# MCU_STM32.net
KiCad netlist of a schematic drawn in Altium Designer
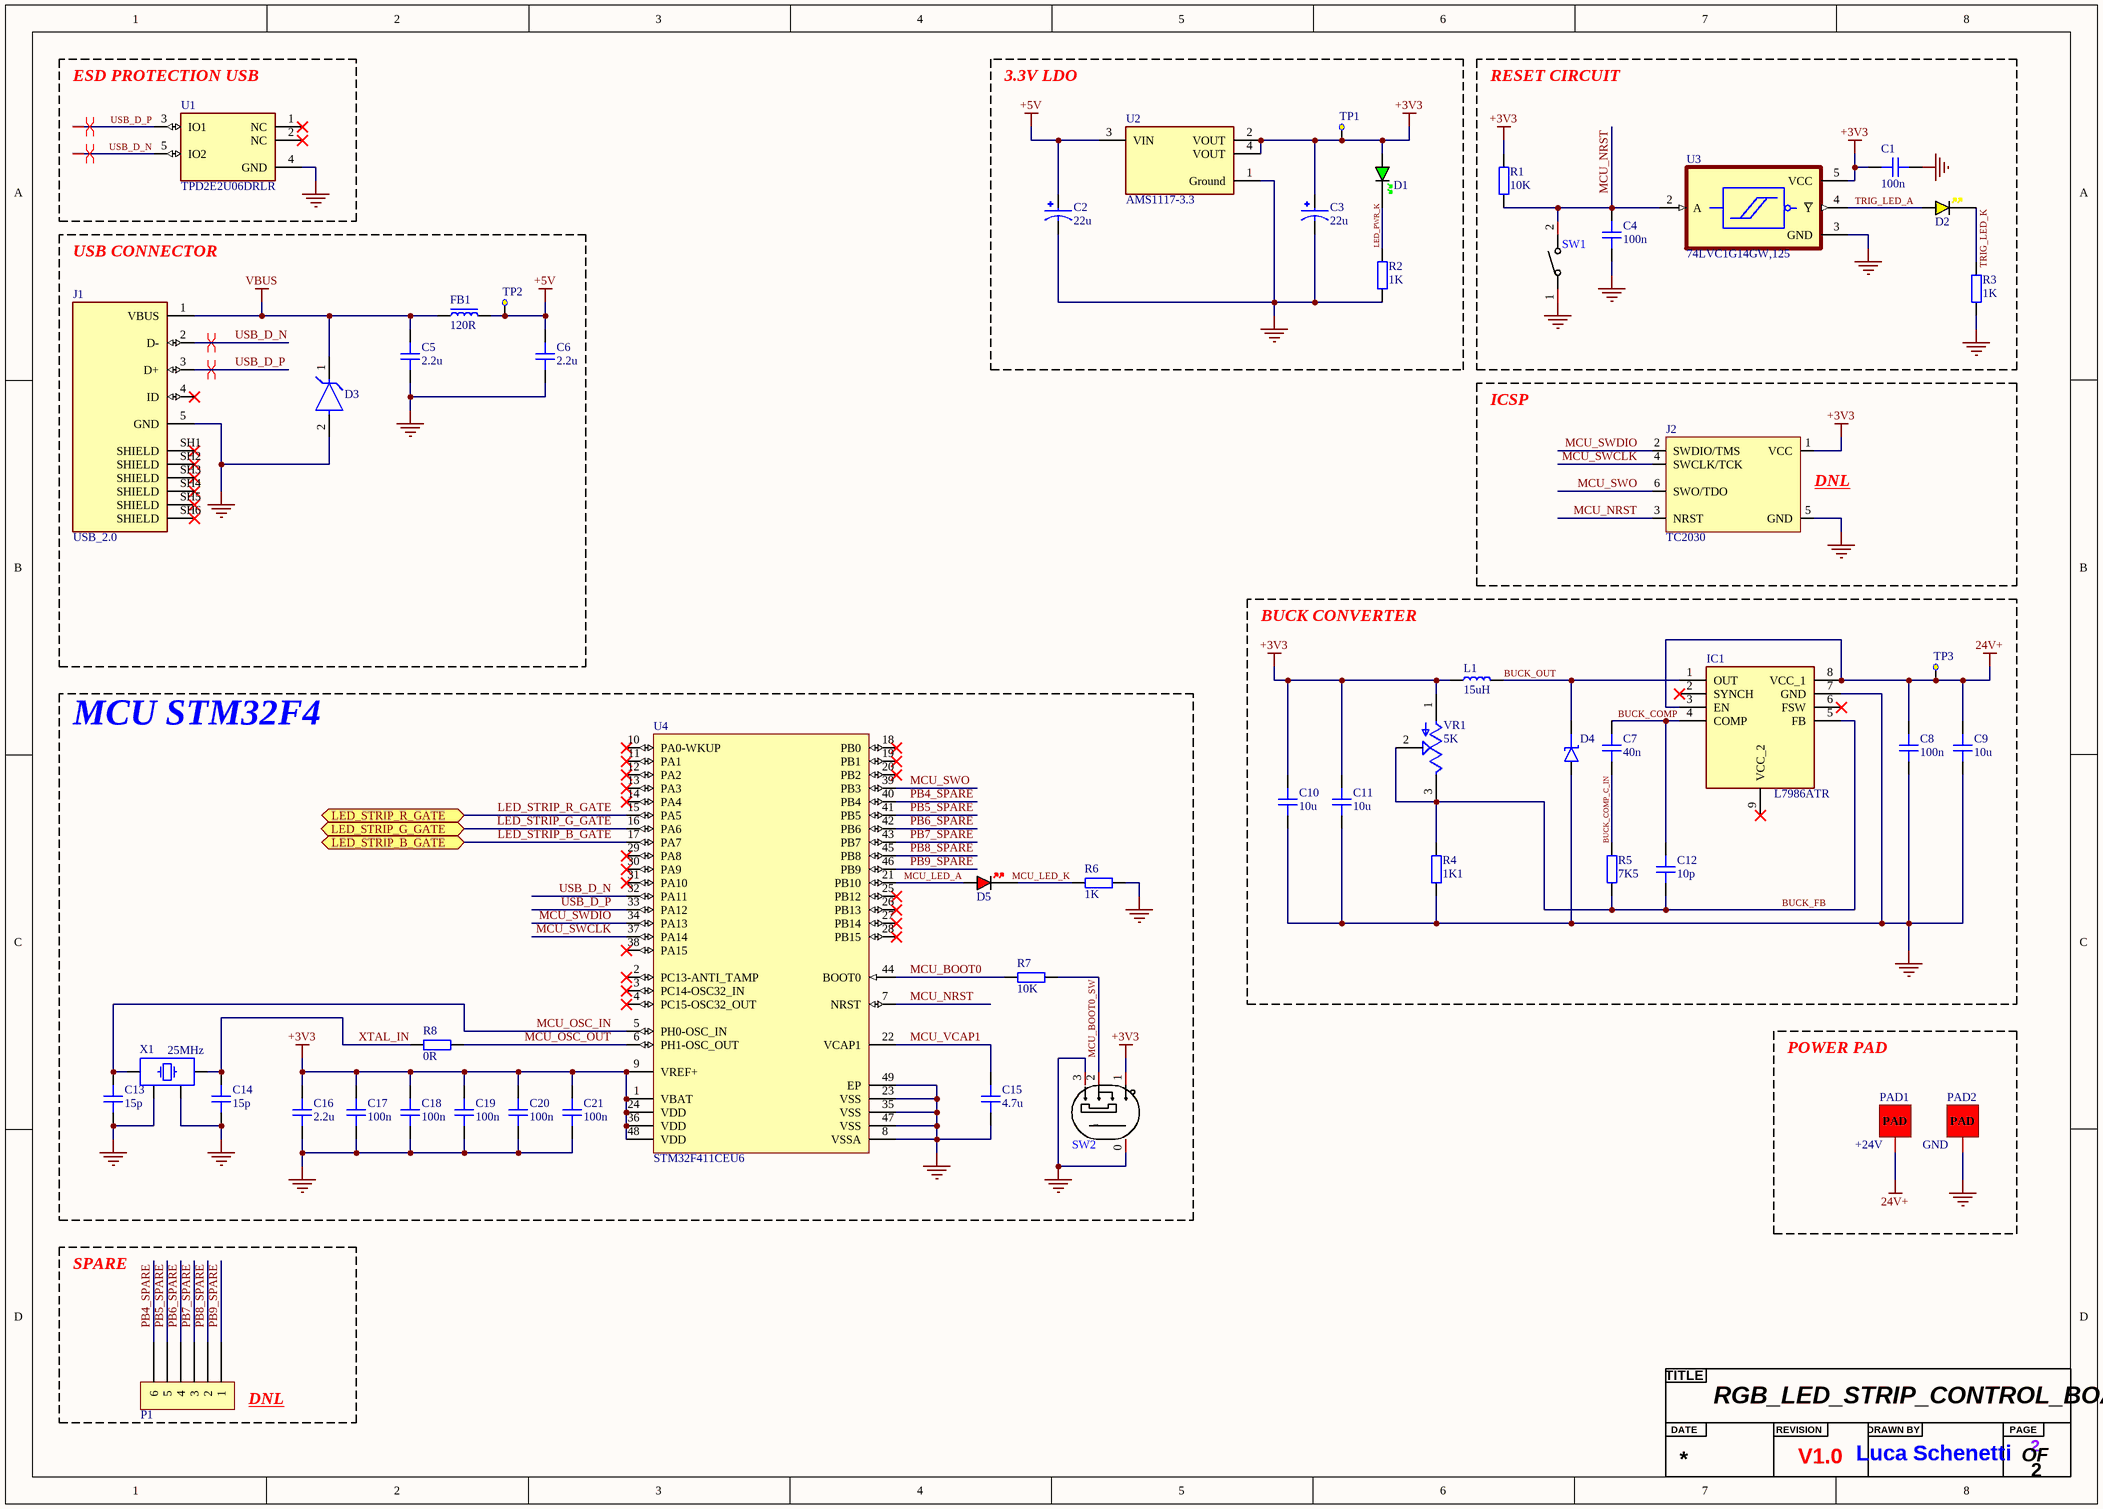
[diagram p0: MCU_STM32.SchDoc]

(export (version "E")
  (design (tool "Eeschema 10.0.6"))
  (components
    (comp (ref "C1")
      (value "100n")
      (footprint "CAP_0402")
      (description "Capacitor SMD 0402 [C1525]")
      (libsource (lib "Schematic-Lib-PhilsLab") (part "CAP_0402"))
    )
    (comp (ref "C2")
      (value "22u")
      (footprint "CAP_EEE1EA220WR")
      (description "Cap Aluminum Lytic 22uF [C2887274]")
      (fields (field (name "MF") "Panasonic") (field (name "DIGI-KEY_PART_NUMBER") "PCE3900TR-ND"))
      (libsource (lib "EEE1EA220WR") (part "EEE1EA220WR"))
    )
    (comp (ref "C3")
      (value "22u")
      (footprint "CAP_EEE1EA220WR")
      (description "Cap Aluminum Lytic 22uF [C2887274]")
      (fields (field (name "MF") "Panasonic") (field (name "DIGI-KEY_PART_NUMBER") "PCE3900TR-ND"))
      (libsource (lib "EEE1EA220WR") (part "EEE1EA220WR"))
    )
    (comp (ref "C4")
      (value "100n")
      (footprint "CAP_0402")
      (description "Capacitor SMD 0402 [C1525]")
      (libsource (lib "Schematic-Lib-PhilsLab") (part "CAP_0402"))
    )
    (comp (ref "C5")
      (value "2.2u")
      (footprint "CAP_0603")
      (description "Capacitor SMD 0603 [C23630]")
      (libsource (lib "Schematic-Lib-PhilsLab") (part "CAP_0603"))
    )
    (comp (ref "C6")
      (value "2.2u")
      (footprint "CAP_0603")
      (description "Capacitor SMD 0603 [C23630]")
      (libsource (lib "Schematic-Lib-PhilsLab") (part "CAP_0603"))
    )
    (comp (ref "C7")
      (value "40n")
      (footprint "CAP_0805")
      (description "Capacitor SMD 0805 [C502151]")
      (libsource (lib "Schematic-Lib-PhilsLab") (part "CAP_0805"))
    )
    (comp (ref "C8")
      (value "100n")
      (footprint "CAP_0805")
      (description "Capacitor SMD [C49678]")
      (libsource (lib "Schematic-Lib-PhilsLab") (part "CAP_0805"))
    )
    (comp (ref "C9")
      (value "10u")
      (footprint "CAP_0805")
      (description "Capacitor SMD [C440198]")
      (libsource (lib "Schematic-Lib-PhilsLab") (part "CAP_0805"))
    )
    (comp (ref "C10")
      (value "10u")
      (footprint "CAP_0805")
      (description "Capacitor SMD [C440198]")
      (libsource (lib "Schematic-Lib-PhilsLab") (part "CAP_0805"))
    )
    (comp (ref "C11")
      (value "10u")
      (footprint "CAP_0805")
      (description "Capacitor SMD [C440198]")
      (libsource (lib "Schematic-Lib-PhilsLab") (part "CAP_0805"))
    )
    (comp (ref "C12")
      (value "10p")
      (footprint "CAP_0402")
      (description "Capacitor SMD 0402 [C32949]")
      (libsource (lib "Schematic-Lib-PhilsLab") (part "CAP_0402"))
    )
    (comp (ref "C13")
      (value "15p")
      (footprint "CAP_0402")
      (description "Capacitor SMD 0402 [C1548]")
      (libsource (lib "Schematic-Lib-PhilsLab") (part "CAP_0402"))
    )
    (comp (ref "C14")
      (value "15p")
      (footprint "CAP_0402")
      (description "Capacitor SMD 0402 [C1548]")
      (libsource (lib "Schematic-Lib-PhilsLab") (part "CAP_0402"))
    )
    (comp (ref "C15")
      (value "4.7u")
      (footprint "CAP_0603")
      (description "Capacitor SMD 0603 [C19666]")
      (libsource (lib "Schematic-Lib-PhilsLab") (part "CAP_0603"))
    )
    (comp (ref "C16")
      (value "2.2u")
      (footprint "CAP_0603")
      (description "Capacitor SMD 0603 [C23630]")
      (libsource (lib "Schematic-Lib-PhilsLab") (part "CAP_0603"))
    )
    (comp (ref "C17")
      (value "100n")
      (footprint "CAP_0402")
      (description "Capacitor SMD 0402 [C1525]")
      (libsource (lib "Schematic-Lib-PhilsLab") (part "CAP_0402"))
    )
    (comp (ref "C18")
      (value "100n")
      (footprint "CAP_0402")
      (description "Capacitor SMD 0402 [C1525]")
      (libsource (lib "Schematic-Lib-PhilsLab") (part "CAP_0402"))
    )
    (comp (ref "C19")
      (value "100n")
      (footprint "CAP_0402")
      (description "Capacitor SMD 0402 [C1525]")
      (libsource (lib "Schematic-Lib-PhilsLab") (part "CAP_0402"))
    )
    (comp (ref "C20")
      (value "100n")
      (footprint "CAP_0402")
      (description "Capacitor SMD 0402 [C1525]")
      (libsource (lib "Schematic-Lib-PhilsLab") (part "CAP_0402"))
    )
    (comp (ref "C21")
      (value "100n")
      (footprint "CAP_0402")
      (description "Capacitor SMD 0402 [C1525]")
      (libsource (lib "Schematic-Lib-PhilsLab") (part "CAP_0402"))
    )
    (comp (ref "D1")
      (value "GREEN")
      (footprint "LED_0603_GREEN")
      (description "LED 0603 GREEN SMD[C2986059]")
      (libsource (lib "Schematic-Lib-PhilsLab") (part "LED_0603_GREEN"))
    )
    (comp (ref "D2")
      (value "YELLOW")
      (footprint "LED_0603_YELLOW")
      (description "LED 0603 YELLOW SMD[C72038]")
      (libsource (lib "Schematic-Lib-PhilsLab") (part "LED_0603_YELLOW"))
    )
    (comp (ref "D3")
      (value "SMAJ5.0A")
      (footprint "FP-SMA-MFG")
      (description "TVS DIODE 5V 9.2V SMA[C2925443]")
      (fields
        (field (name "MANUFACTURER") "Diodes Inc.")
        (field (name "MANUFACTURER PART NUMBER") "SMAJ5.0A-13-F")
      )
      (libsource (lib "Altium Content Vault") (part "f813f71cba58e380607f5dd3caf9714"))
    )
    (comp (ref "D4")
      (value "~")
      (footprint "DO-214AC-2 (SMA)")
      (description "Diode Schottky SMD SMA (DO-214AA)[C8678]")
      (libsource (lib "Schematic-Lib-PhilsLab") (part "D_SCHOTTKY_SMA"))
    )
    (comp (ref "D5")
      (value "RED")
      (footprint "LED_0603_RED")
      (description "LED 0603 RED SMD[C2926776]")
      (libsource (lib "Schematic-Lib-PhilsLab") (part "LED_0603_RED"))
    )
    (comp (ref "FB1")
      (value "120R")
      (footprint "FB_0603")
      (description "Ferrite Bead SMD 0603[C14709]")
      (libsource (lib "Schematic-Lib-PhilsLab") (part "FB_0603"))
    )
    (comp (ref "IC1")
      (value "L7986ATR")
      (footprint "SamacSys:SOIC127P600X170-9N")
      (description "Integrated Circuit")
      (fields (field (name "MOUSER PART NUMBER") "511-L7986ATR"))
      (libsource (lib "SamacSys") (part "L7986ATR"))
    )
    (comp (ref "J1")
      (value "USB_2.0")
      (footprint "USB_2.0")
      (description "[C132563]")
      (libsource (lib "SchedaLed") (part "USB_2.0"))
    )
    (comp (ref "J2")
      (value "TC2030")
      (footprint "TC2030-FP")
      (description "Tag-Connect No-Solder SWD Debug Connector DO NOT PLACE")
      (fields (field (name "MANUFACTURER") "Tag-Connect"))
      (libsource (lib "Schematic-Lib-PhilsLab") (part "TC2030"))
    )
    (comp (ref "L1")
      (value "15uH")
      (footprint "Footprint-Lib-PhilsLab:FXL0630-150-M")
      (description "Power Inductor SMD [C177243]")
      (fields
        (field (name "MANUFACTURER") "cjiang (Changjiang Microelectronics Tech)")
        (field (name "MANUFACTURER PART NUMBER") "FXL0630-150-M")
      )
      (libsource (lib "Schematic-Lib-PhilsLab") (part "FXL0630-150-M"))
    )
    (comp (ref "P1")
      (value "~")
      (footprint "Header 1x6 male")
      (description "[C37208]")
      (libsource (lib "Headers") (part "Header 1x6"))
    )
    (comp (ref "PAD1") (value "+24V") (footprint "PAD_PWR") (libsource (lib "SchedaLed") (part "PAD_PWR")))
    (comp (ref "PAD2") (value "GND") (footprint "PAD_PWR") (libsource (lib "SchedaLed") (part "PAD_PWR")))
    (comp (ref "R1")
      (value "10K")
      (footprint "RES_0402")
      (description "Resistor SMD 0402 [C25744]")
      (libsource (lib "Schematic-Lib-PhilsLab") (part "RES_0402"))
    )
    (comp (ref "R2")
      (value "1K")
      (footprint "RES_0402")
      (description "Resistor SMD 0402 [C11702]")
      (libsource (lib "Schematic-Lib-PhilsLab") (part "RES_0402"))
    )
    (comp (ref "R3")
      (value "1K")
      (footprint "RES_0402")
      (description "Resistor SMD 0402 [C11702]")
      (libsource (lib "Schematic-Lib-PhilsLab") (part "RES_0402"))
    )
    (comp (ref "R4")
      (value "1K1")
      (footprint "RES_0603")
      (description "Resistor SMD 0603[C22764]")
      (libsource (lib "Schematic-Lib-PhilsLab") (part "RES_0603"))
    )
    (comp (ref "R5")
      (value "7K5")
      (footprint "RES_0603")
      (description "Resistor SMD 0603[C23234]")
      (libsource (lib "Schematic-Lib-PhilsLab") (part "RES_0603"))
    )
    (comp (ref "R6")
      (value "1K")
      (footprint "RES_0402")
      (description "Resistor SMD 0402 [C11702]")
      (libsource (lib "Schematic-Lib-PhilsLab") (part "RES_0402"))
    )
    (comp (ref "R7")
      (value "10K")
      (footprint "RES_0402")
      (description "Resistor SMD 0402 [C25744]")
      (libsource (lib "Schematic-Lib-PhilsLab") (part "RES_0402"))
    )
    (comp (ref "R8")
      (value "0R")
      (footprint "RES_0402")
      (description "Resistor SMD 0402 [C17168]")
      (libsource (lib "Schematic-Lib-PhilsLab") (part "RES_0402"))
    )
    (comp (ref "SW1")
      (value "TS-1088-AR02016")
      (footprint "TS-1088-AR02016")
      (fields (field (name "MANUFACTURER") "XUNPU(讯普)"))
      (libsource (lib "SchedaLed") (part "TS-1088-AR02016"))
    )
    (comp (ref "SW2")
      (value "SK-3296S-01-L1")
      (footprint "SW-SMD_3P-P1.50_L2.7-W6.6")
      (fields (field (name "MANUFACTURER") "XKB Connectivity(中国星坤)"))
      (libsource (lib "SchedaLed") (part "SK-3296S-01-L1"))
    )
    (comp (ref "TP1")
      (value "Test Point")
      (footprint "Test Point")
      (libsource (lib "SchedaLed") (part "Test Point"))
    )
    (comp (ref "TP2")
      (value "Test Point")
      (footprint "Test Point")
      (libsource (lib "SchedaLed") (part "Test Point"))
    )
    (comp (ref "TP3")
      (value "Test Point")
      (footprint "Test Point")
      (libsource (lib "SchedaLed") (part "Test Point"))
    )
    (comp (ref "U1")
      (value "TPD2E2U06DRLR")
      (footprint "FP-DRL0005A-MFG")
      (description "TVS DIODE 5.5V 12.4V SOT5[C1855726]")
      (fields
        (field (name "OCTOPART") "https://octopart.com/tpd2e2u06drlr-texas+instruments-47095345")
        (field (name "MANUFACTURER") "Texas Instruments")
      )
      (libsource (lib "Altium Content Vault") (part "e208c5e9626b0fa1527e6459d6846dc"))
    )
    (comp (ref "U2")
      (value "AMS1117-3.3")
      (footprint "FP-AMS1117-IPC_C")
      (description "LDO Voltage Regulators 1A, 3.3V [C6186]")
      (fields
        (field (name "OCTOPART") "https://octopart.com/ams1117-3.3-advanced+monolithic+systems-25899300")
        (field (name "MANUFACTURER") "Advanced Monolithic Systems")
      )
      (libsource (lib "Altium Content Vault") (part "8bdbb5f8e77002000e30dd2845d0354"))
    )
    (comp (ref "U3")
      (value "74LVC1G14GW,125")
      (footprint "SOT65P212X110-5N")
      (description "Inverter Schmitt Trigger 1-Element CMOS 5-Pin TSSOP T/R")
      (libsource (lib "74LVC1G14GW_125") (part "74LVC1G14GW,125"))
    )
    (comp (ref "U4")
      (value "STM32F411CEU6")
      (footprint "STM-UFQFPN48_L")
      (libsource (lib "Altium Content Vault") (part "MC-ARM-STM32F411-UFQFPN48"))
    )
    (comp (ref "VR1")
      (value "5K")
      (footprint "TRIM_3362P-1-502LF")
      (description "Trimmer, Cermet, Rest 5 Kilohms, PCB, 1 Turns, Pwr-Rtg 0.5 W, Tol 10% ¦ Bourns 3362P-1-502LF")
      (fields (field (name "MF") "Bourns") (field (name "MP") "3362P-1-502LF"))
      (libsource (lib "3362P-1-502LF") (part "3362P-1-502LF"))
    )
    (comp (ref "X1")
      (value "25MHz")
      (footprint "XTAL_3225")
      (description "Crystal SMD 24MHz 10PPM 7pF 3225 [C9006]")
      (fields
        (field (name "MANUFACTURER") "Epson")
        (field (name "MANUFACTURER PART NUMBER") "TSX-3225 24.0000MF15X-AC")
      )
      (libsource (lib "Schematic-Lib-PhilsLab") (part "TSX-3225_24.0000MF15X-AC"))
    )
  )
  (nets
    (net (code "1") (name "+3V3") (class "Default")
      (node (ref "C1") (pin "2") (pinfunction "2_2") (pintype "passive"))
      (node (ref "C10") (pin "2") (pinfunction "2_2") (pintype "passive"))
      (node (ref "C11") (pin "2") (pinfunction "2_2") (pintype "passive"))
      (node (ref "C16") (pin "2") (pinfunction "2_2") (pintype "passive"))
      (node (ref "C17") (pin "2") (pinfunction "2_2") (pintype "passive"))
      (node (ref "C18") (pin "2") (pinfunction "2_2") (pintype "passive"))
      (node (ref "C19") (pin "2") (pinfunction "2_2") (pintype "passive"))
      (node (ref "C20") (pin "2") (pinfunction "2_2") (pintype "passive"))
      (node (ref "C21") (pin "2") (pinfunction "2_2") (pintype "passive"))
      (node (ref "C3") (pin "1") (pinfunction "1_1") (pintype "passive"))
      (node (ref "D1") (pin "A") (pinfunction "A_A") (pintype "passive"))
      (node (ref "J2") (pin "1") (pinfunction "VCC_1") (pintype "passive"))
      (node (ref "L1") (pin "1") (pinfunction "1_1") (pintype "passive"))
      (node (ref "R1") (pin "2") (pinfunction "2_2") (pintype "passive"))
      (node (ref "SW2") (pin "1") (pinfunction "1_1") (pintype "passive"))
      (node (ref "TP1") (pin "1") (pinfunction "Test_Point_1") (pintype "passive"))
      (node (ref "U2") (pin "2") (pinfunction "VOUT_2") (pintype "passive"))
      (node (ref "U2") (pin "4") (pinfunction "VOUT_4") (pintype "passive"))
      (node (ref "U3") (pin "5") (pinfunction "VCC_5") (pintype "power_in"))
      (node (ref "U4") (pin "1") (pinfunction "VBAT_1") (pintype "power_in"))
      (node (ref "U4") (pin "24") (pinfunction "VDD_24") (pintype "power_in"))
      (node (ref "U4") (pin "36") (pinfunction "VDD_36") (pintype "power_in"))
      (node (ref "U4") (pin "48") (pinfunction "VDD_48") (pintype "power_in"))
      (node (ref "U4") (pin "9") (pinfunction "VREF+_9") (pintype "power_in"))
      (node (ref "VR1") (pin "1") (pinfunction "CCW_1") (pintype "passive"))
    )
    (net (code "2") (name "+5V") (class "Default")
      (node (ref "C2") (pin "1") (pinfunction "1_1") (pintype "passive"))
      (node (ref "C6") (pin "2") (pinfunction "2_2") (pintype "passive"))
      (node (ref "FB1") (pin "2") (pinfunction "2_2") (pintype "passive"))
      (node (ref "TP2") (pin "1") (pinfunction "Test_Point_1") (pintype "passive"))
      (node (ref "U2") (pin "3") (pinfunction "VIN_3") (pintype "power_in"))
    )
    (net (code "3") (name "/BUCK_COMP") (class "Default")
      (node (ref "C12") (pin "2") (pinfunction "2_2") (pintype "passive"))
      (node (ref "C7") (pin "2") (pinfunction "2_2") (pintype "passive"))
      (node (ref "IC1") (pin "4") (pinfunction "COMP_4") (pintype "passive"))
    )
    (net (code "4") (name "/BUCK_COMP_C_IN") (class "Default")
      (node (ref "C7") (pin "1") (pinfunction "1_1") (pintype "passive"))
      (node (ref "R5") (pin "2") (pinfunction "2_2") (pintype "passive"))
    )
    (net (code "5") (name "/BUCK_FB") (class "Default")
      (node (ref "C12") (pin "1") (pinfunction "1_1") (pintype "passive"))
      (node (ref "IC1") (pin "5") (pinfunction "FB_5") (pintype "passive"))
      (node (ref "R4") (pin "2") (pinfunction "2_2") (pintype "passive"))
      (node (ref "R5") (pin "1") (pinfunction "1_1") (pintype "passive"))
      (node (ref "VR1") (pin "2") (pinfunction "WIPER_2") (pintype "passive"))
      (node (ref "VR1") (pin "3") (pinfunction "CW_3") (pintype "passive"))
    )
    (net (code "6") (name "/BUCK_OUT") (class "Default")
      (node (ref "D4") (pin "K") (pinfunction "K_K") (pintype "passive"))
      (node (ref "IC1") (pin "1") (pinfunction "OUT_1") (pintype "passive"))
      (node (ref "L1") (pin "2") (pinfunction "2_2") (pintype "passive"))
    )
    (net (code "7") (name "/LED_PWR_K") (class "Default")
      (node (ref "D1") (pin "K") (pinfunction "K_K") (pintype "passive"))
      (node (ref "R2") (pin "2") (pinfunction "2_2") (pintype "passive"))
    )
    (net (code "8") (name "/LED_STRIP_B_GATE") (class "Default")
      (node (ref "U4") (pin "17") (pinfunction "PA7_17") (pintype "bidirectional"))
    )
    (net (code "9") (name "/LED_STRIP_G_GATE") (class "Default")
      (node (ref "U4") (pin "16") (pinfunction "PA6_16") (pintype "bidirectional"))
    )
    (net (code "10") (name "/LED_STRIP_R_GATE") (class "Default")
      (node (ref "U4") (pin "15") (pinfunction "PA5_15") (pintype "bidirectional"))
    )
    (net (code "11") (name "/MCU_BOOT0") (class "Default")
      (node (ref "R7") (pin "2") (pinfunction "2_2") (pintype "passive"))
      (node (ref "U4") (pin "44") (pinfunction "BOOT0_44") (pintype "input"))
    )
    (net (code "12") (name "/MCU_BOOT0_SW") (class "Default")
      (node (ref "R7") (pin "1") (pinfunction "1_1") (pintype "passive"))
      (node (ref "SW2") (pin "2") (pinfunction "2_2") (pintype "passive"))
    )
    (net (code "13") (name "/MCU_LED_A") (class "Default")
      (node (ref "D5") (pin "A") (pinfunction "A_A") (pintype "passive"))
      (node (ref "U4") (pin "21") (pinfunction "PB10_21") (pintype "bidirectional"))
    )
    (net (code "14") (name "/MCU_LED_K") (class "Default")
      (node (ref "D5") (pin "K") (pinfunction "K_K") (pintype "passive"))
      (node (ref "R6") (pin "2") (pinfunction "2_2") (pintype "passive"))
    )
    (net (code "15") (name "/MCU_NRST") (class "Default")
      (node (ref "C4") (pin "2") (pinfunction "2_2") (pintype "passive"))
      (node (ref "J2") (pin "3") (pinfunction "NRST_3") (pintype "passive"))
      (node (ref "R1") (pin "1") (pinfunction "1_1") (pintype "passive"))
      (node (ref "SW1") (pin "2") (pinfunction "2_2") (pintype "passive"))
      (node (ref "U3") (pin "2") (pinfunction "A_2") (pintype "input"))
      (node (ref "U4") (pin "7") (pinfunction "NRST_7") (pintype "bidirectional"))
    )
    (net (code "16") (name "/MCU_OSC_IN") (class "Default")
      (node (ref "C13") (pin "2") (pinfunction "2_2") (pintype "passive"))
      (node (ref "U4") (pin "5") (pinfunction "PH0-OSC_IN_5") (pintype "bidirectional"))
      (node (ref "X1") (pin "1") (pinfunction "1_1") (pintype "passive"))
    )
    (net (code "17") (name "/MCU_OSC_OUT") (class "Default")
      (node (ref "R8") (pin "1") (pinfunction "1_1") (pintype "passive"))
      (node (ref "U4") (pin "6") (pinfunction "PH1-OSC_OUT_6") (pintype "bidirectional"))
    )
    (net (code "18") (name "/MCU_SWCLK") (class "Default")
      (node (ref "J2") (pin "4") (pinfunction "SWCLK/TCK_4") (pintype "passive"))
      (node (ref "U4") (pin "37") (pinfunction "PA14_37") (pintype "bidirectional"))
    )
    (net (code "19") (name "/MCU_SWDIO") (class "Default")
      (node (ref "J2") (pin "2") (pinfunction "SWDIO/TMS_2") (pintype "passive"))
      (node (ref "U4") (pin "34") (pinfunction "PA13_34") (pintype "bidirectional"))
    )
    (net (code "20") (name "/MCU_SWO") (class "Default")
      (node (ref "J2") (pin "6") (pinfunction "SWO/TDO_6") (pintype "passive"))
      (node (ref "U4") (pin "39") (pinfunction "PB3_39") (pintype "bidirectional"))
    )
    (net (code "21") (name "/MCU_VCAP1") (class "Default")
      (node (ref "C15") (pin "2") (pinfunction "2_2") (pintype "passive"))
      (node (ref "U4") (pin "22") (pinfunction "VCAP1_22") (pintype "passive"))
    )
    (net (code "22") (name "/PB4_SPARE") (class "Default")
      (node (ref "P1") (pin "6") (pinfunction "6_6") (pintype "passive"))
      (node (ref "U4") (pin "40") (pinfunction "PB4_40") (pintype "bidirectional"))
    )
    (net (code "23") (name "/PB5_SPARE") (class "Default")
      (node (ref "P1") (pin "5") (pinfunction "5_5") (pintype "passive"))
      (node (ref "U4") (pin "41") (pinfunction "PB5_41") (pintype "bidirectional"))
    )
    (net (code "24") (name "/PB6_SPARE") (class "Default")
      (node (ref "P1") (pin "4") (pinfunction "4_4") (pintype "passive"))
      (node (ref "U4") (pin "42") (pinfunction "PB6_42") (pintype "bidirectional"))
    )
    (net (code "25") (name "/PB7_SPARE") (class "Default")
      (node (ref "P1") (pin "3") (pinfunction "3_3") (pintype "passive"))
      (node (ref "U4") (pin "43") (pinfunction "PB7_43") (pintype "bidirectional"))
    )
    (net (code "26") (name "/PB8_SPARE") (class "Default")
      (node (ref "P1") (pin "2") (pinfunction "2_2") (pintype "passive"))
      (node (ref "U4") (pin "45") (pinfunction "PB8_45") (pintype "bidirectional"))
    )
    (net (code "27") (name "/PB9_SPARE") (class "Default")
      (node (ref "P1") (pin "1") (pinfunction "1_1") (pintype "passive"))
      (node (ref "U4") (pin "46") (pinfunction "PB9_46") (pintype "bidirectional"))
    )
    (net (code "28") (name "/TRIG_LED_A") (class "Default")
      (node (ref "D2") (pin "A") (pinfunction "A_A") (pintype "passive"))
      (node (ref "U3") (pin "4") (pinfunction "~{Y}_4") (pintype "output"))
    )
    (net (code "29") (name "/TRIG_LED_K") (class "Default")
      (node (ref "D2") (pin "K") (pinfunction "K_K") (pintype "passive"))
      (node (ref "R3") (pin "2") (pinfunction "2_2") (pintype "passive"))
    )
    (net (code "30") (name "/USB_D_N") (class "Default")
      (node (ref "J1") (pin "2") (pinfunction "D-_2") (pintype "bidirectional"))
      (node (ref "U1") (pin "5") (pinfunction "IO2_5") (pintype "bidirectional"))
      (node (ref "U4") (pin "32") (pinfunction "PA11_32") (pintype "bidirectional"))
    )
    (net (code "31") (name "/USB_D_P") (class "Default")
      (node (ref "J1") (pin "3") (pinfunction "D+_3") (pintype "bidirectional"))
      (node (ref "U1") (pin "3") (pinfunction "IO1_3") (pintype "bidirectional"))
      (node (ref "U4") (pin "33") (pinfunction "PA12_33") (pintype "bidirectional"))
    )
    (net (code "32") (name "/XTAL_IN") (class "Default")
      (node (ref "C14") (pin "2") (pinfunction "2_2") (pintype "passive"))
      (node (ref "R8") (pin "2") (pinfunction "2_2") (pintype "passive"))
      (node (ref "X1") (pin "3") (pinfunction "3_3") (pintype "passive"))
    )
    (net (code "33") (name "24V+") (class "Default")
      (node (ref "C8") (pin "2") (pinfunction "2_2") (pintype "passive"))
      (node (ref "C9") (pin "2") (pinfunction "2_2") (pintype "passive"))
      (node (ref "IC1") (pin "3") (pinfunction "EN_3") (pintype "passive"))
      (node (ref "IC1") (pin "8") (pinfunction "VCC_1_8") (pintype "passive"))
      (node (ref "PAD1") (pin "1") (pinfunction "PAD_1") (pintype "passive"))
      (node (ref "TP3") (pin "1") (pinfunction "Test_Point_1") (pintype "passive"))
    )
    (net (code "34") (name "GND") (class "Default")
      (node (ref "C1") (pin "1") (pinfunction "1_1") (pintype "passive"))
      (node (ref "C10") (pin "1") (pinfunction "1_1") (pintype "passive"))
      (node (ref "C11") (pin "1") (pinfunction "1_1") (pintype "passive"))
      (node (ref "C13") (pin "1") (pinfunction "1_1") (pintype "passive"))
      (node (ref "C14") (pin "1") (pinfunction "1_1") (pintype "passive"))
      (node (ref "C15") (pin "1") (pinfunction "1_1") (pintype "passive"))
      (node (ref "C16") (pin "1") (pinfunction "1_1") (pintype "passive"))
      (node (ref "C17") (pin "1") (pinfunction "1_1") (pintype "passive"))
      (node (ref "C18") (pin "1") (pinfunction "1_1") (pintype "passive"))
      (node (ref "C19") (pin "1") (pinfunction "1_1") (pintype "passive"))
      (node (ref "C2") (pin "2") (pinfunction "2_2") (pintype "passive"))
      (node (ref "C20") (pin "1") (pinfunction "1_1") (pintype "passive"))
      (node (ref "C21") (pin "1") (pinfunction "1_1") (pintype "passive"))
      (node (ref "C3") (pin "2") (pinfunction "2_2") (pintype "passive"))
      (node (ref "C4") (pin "1") (pinfunction "1_1") (pintype "passive"))
      (node (ref "C5") (pin "1") (pinfunction "1_1") (pintype "passive"))
      (node (ref "C6") (pin "1") (pinfunction "1_1") (pintype "passive"))
      (node (ref "C8") (pin "1") (pinfunction "1_1") (pintype "passive"))
      (node (ref "C9") (pin "1") (pinfunction "1_1") (pintype "passive"))
      (node (ref "D3") (pin "2") (pinfunction "A_2") (pintype "passive"))
      (node (ref "D4") (pin "A") (pinfunction "A_A") (pintype "passive"))
      (node (ref "IC1") (pin "7") (pinfunction "GND_7") (pintype "passive"))
      (node (ref "J1") (pin "5") (pinfunction "GND_5") (pintype "power_in"))
      (node (ref "J2") (pin "5") (pinfunction "GND_5") (pintype "passive"))
      (node (ref "PAD2") (pin "1") (pinfunction "PAD_1") (pintype "passive"))
      (node (ref "R2") (pin "1") (pinfunction "1_1") (pintype "passive"))
      (node (ref "R3") (pin "1") (pinfunction "1_1") (pintype "passive"))
      (node (ref "R4") (pin "1") (pinfunction "1_1") (pintype "passive"))
      (node (ref "R6") (pin "1") (pinfunction "1_1") (pintype "passive"))
      (node (ref "SW1") (pin "1") (pinfunction "1_1") (pintype "passive"))
      (node (ref "SW2") (pin "0") (pinfunction "0_0") (pintype "passive"))
      (node (ref "SW2") (pin "3") (pinfunction "3_3") (pintype "passive"))
      (node (ref "U1") (pin "4") (pinfunction "GND_4") (pintype "power_in"))
      (node (ref "U2") (pin "1") (pinfunction "Ground_1") (pintype "power_in"))
      (node (ref "U3") (pin "3") (pinfunction "GND_3") (pintype "power_in"))
      (node (ref "U4") (pin "23") (pinfunction "VSS_23") (pintype "power_in"))
      (node (ref "U4") (pin "35") (pinfunction "VSS_35") (pintype "power_in"))
      (node (ref "U4") (pin "47") (pinfunction "VSS_47") (pintype "power_in"))
      (node (ref "U4") (pin "49") (pinfunction "EP_49") (pintype "power_in"))
      (node (ref "U4") (pin "8") (pinfunction "VSSA_8") (pintype "power_in"))
      (node (ref "X1") (pin "2") (pinfunction "2_2") (pintype "passive"))
      (node (ref "X1") (pin "4") (pinfunction "4_4") (pintype "passive"))
    )
    (net (code "35") (name "VBUS") (class "Default")
      (node (ref "C5") (pin "2") (pinfunction "2_2") (pintype "passive"))
      (node (ref "D3") (pin "1") (pinfunction "C_1") (pintype "passive"))
      (node (ref "FB1") (pin "1") (pinfunction "1_1") (pintype "passive"))
      (node (ref "J1") (pin "1") (pinfunction "VBUS_1") (pintype "power_in"))
    )
    (net (code "36") (name "unconnected-(IC1-FSW-Pad6)") (class "Default")
      (node (ref "IC1") (pin "6") (pinfunction "FSW_6") (pintype "passive+no_connect"))
    )
    (net (code "37") (name "unconnected-(IC1-SYNCH-Pad2)") (class "Default")
      (node (ref "IC1") (pin "2") (pinfunction "SYNCH_2") (pintype "passive+no_connect"))
    )
    (net (code "38") (name "unconnected-(IC1-VCC_2-Pad9)") (class "Default")
      (node (ref "IC1") (pin "9") (pinfunction "VCC_2_9") (pintype "passive+no_connect"))
    )
    (net (code "39") (name "unconnected-(J1-ID-Pad4)") (class "Default")
      (node (ref "J1") (pin "4") (pinfunction "ID_4") (pintype "bidirectional+no_connect"))
    )
    (net (code "40") (name "unconnected-(J1-SHIELD-PadSH1)") (class "Default")
      (node (ref "J1") (pin "SH1") (pinfunction "SHIELD_SH1") (pintype "passive+no_connect"))
    )
    (net (code "41") (name "unconnected-(J1-SHIELD-PadSH2)") (class "Default")
      (node (ref "J1") (pin "SH2") (pinfunction "SHIELD_SH2") (pintype "passive+no_connect"))
    )
    (net (code "42") (name "unconnected-(J1-SHIELD-PadSH3)") (class "Default")
      (node (ref "J1") (pin "SH3") (pinfunction "SHIELD_SH3") (pintype "passive+no_connect"))
    )
    (net (code "43") (name "unconnected-(J1-SHIELD-PadSH4)") (class "Default")
      (node (ref "J1") (pin "SH4") (pinfunction "SHIELD_SH4") (pintype "passive+no_connect"))
    )
    (net (code "44") (name "unconnected-(J1-SHIELD-PadSH5)") (class "Default")
      (node (ref "J1") (pin "SH5") (pinfunction "SHIELD_SH5") (pintype "passive+no_connect"))
    )
    (net (code "45") (name "unconnected-(J1-SHIELD-PadSH6)") (class "Default")
      (node (ref "J1") (pin "SH6") (pinfunction "SHIELD_SH6") (pintype "passive+no_connect"))
    )
    (net (code "46") (name "unconnected-(U1-NC-Pad1)") (class "Default")
      (node (ref "U1") (pin "1") (pinfunction "NC_1") (pintype "passive+no_connect"))
    )
    (net (code "47") (name "unconnected-(U1-NC-Pad2)") (class "Default")
      (node (ref "U1") (pin "2") (pinfunction "NC_2") (pintype "passive+no_connect"))
    )
    (net (code "48") (name "unconnected-(U4-PA0-WKUP-Pad10)") (class "Default")
      (node (ref "U4") (pin "10") (pinfunction "PA0-WKUP_10") (pintype "bidirectional+no_connect"))
    )
    (net (code "49") (name "unconnected-(U4-PA1-Pad11)") (class "Default")
      (node (ref "U4") (pin "11") (pinfunction "PA1_11") (pintype "bidirectional+no_connect"))
    )
    (net (code "50") (name "unconnected-(U4-PA2-Pad12)") (class "Default")
      (node (ref "U4") (pin "12") (pinfunction "PA2_12") (pintype "bidirectional+no_connect"))
    )
    (net (code "51") (name "unconnected-(U4-PA3-Pad13)") (class "Default")
      (node (ref "U4") (pin "13") (pinfunction "PA3_13") (pintype "bidirectional+no_connect"))
    )
    (net (code "52") (name "unconnected-(U4-PA4-Pad14)") (class "Default")
      (node (ref "U4") (pin "14") (pinfunction "PA4_14") (pintype "bidirectional+no_connect"))
    )
    (net (code "53") (name "unconnected-(U4-PA8-Pad29)") (class "Default")
      (node (ref "U4") (pin "29") (pinfunction "PA8_29") (pintype "bidirectional+no_connect"))
    )
    (net (code "54") (name "unconnected-(U4-PA9-Pad30)") (class "Default")
      (node (ref "U4") (pin "30") (pinfunction "PA9_30") (pintype "bidirectional+no_connect"))
    )
    (net (code "55") (name "unconnected-(U4-PA10-Pad31)") (class "Default")
      (node (ref "U4") (pin "31") (pinfunction "PA10_31") (pintype "bidirectional+no_connect"))
    )
    (net (code "56") (name "unconnected-(U4-PA15-Pad38)") (class "Default")
      (node (ref "U4") (pin "38") (pinfunction "PA15_38") (pintype "bidirectional+no_connect"))
    )
    (net (code "57") (name "unconnected-(U4-PB0-Pad18)") (class "Default")
      (node (ref "U4") (pin "18") (pinfunction "PB0_18") (pintype "bidirectional+no_connect"))
    )
    (net (code "58") (name "unconnected-(U4-PB1-Pad19)") (class "Default")
      (node (ref "U4") (pin "19") (pinfunction "PB1_19") (pintype "bidirectional+no_connect"))
    )
    (net (code "59") (name "unconnected-(U4-PB2-Pad20)") (class "Default")
      (node (ref "U4") (pin "20") (pinfunction "PB2_20") (pintype "bidirectional+no_connect"))
    )
    (net (code "60") (name "unconnected-(U4-PB12-Pad25)") (class "Default")
      (node (ref "U4") (pin "25") (pinfunction "PB12_25") (pintype "bidirectional+no_connect"))
    )
    (net (code "61") (name "unconnected-(U4-PB13-Pad26)") (class "Default")
      (node (ref "U4") (pin "26") (pinfunction "PB13_26") (pintype "bidirectional+no_connect"))
    )
    (net (code "62") (name "unconnected-(U4-PB14-Pad27)") (class "Default")
      (node (ref "U4") (pin "27") (pinfunction "PB14_27") (pintype "bidirectional+no_connect"))
    )
    (net (code "63") (name "unconnected-(U4-PB15-Pad28)") (class "Default")
      (node (ref "U4") (pin "28") (pinfunction "PB15_28") (pintype "bidirectional+no_connect"))
    )
    (net (code "64") (name "unconnected-(U4-PC13-ANTI_TAMP-Pad2)") (class "Default")
      (node (ref "U4") (pin "2") (pinfunction "PC13-ANTI_TAMP_2") (pintype "bidirectional+no_connect"))
    )
    (net (code "65") (name "unconnected-(U4-PC14-OSC32_IN-Pad3)") (class "Default")
      (node (ref "U4") (pin "3") (pinfunction "PC14-OSC32_IN_3") (pintype "bidirectional+no_connect"))
    )
    (net (code "66") (name "unconnected-(U4-PC15-OSC32_OUT-Pad4)") (class "Default")
      (node (ref "U4") (pin "4") (pinfunction "PC15-OSC32_OUT_4") (pintype "bidirectional+no_connect"))
    )
  )
)
